# Charger.net
KiCad netlist of a schematic drawn in Altium Designer
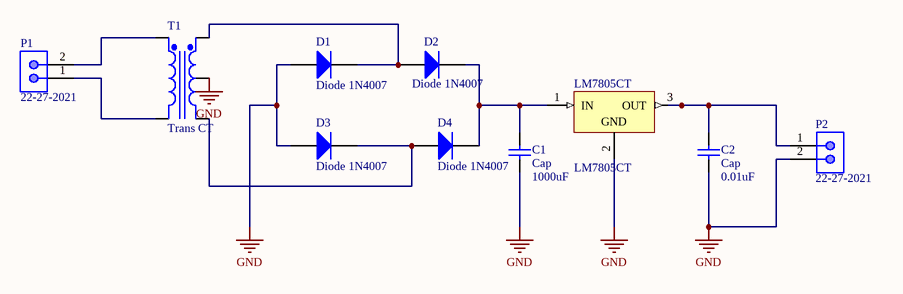
[diagram p0: Charger.SchDoc]

(export (version "E")
  (design (tool "Eeschema 10.0.6"))
  (components
    (comp (ref "C1")
      (value "Cap")
      (footprint "RAD-0.3")
      (description "Capacitor")
      (fields (field (name "ALTIUM_VALUE") "1000uF") (field (name "PUBLISHER") "Altium Limited"))
      (libsource (lib "Miscellaneous Devices") (part "Cap"))
    )
    (comp (ref "C2")
      (value "Cap")
      (footprint "RAD-0.3")
      (description "Capacitor")
      (fields (field (name "ALTIUM_VALUE") "0.01uF") (field (name "PUBLISHER") "Altium Limited"))
      (libsource (lib "Miscellaneous Devices") (part "Cap"))
    )
    (comp (ref "D1")
      (value "Diode 1N4007")
      (footprint "DO-41")
      (description "1 Amp General Purpose Rectifier")
      (fields (field (name "PUBLISHER") "Altium Limited"))
      (libsource (lib "Miscellaneous Devices") (part "Diode 1N4007"))
    )
    (comp (ref "D2")
      (value "Diode 1N4007")
      (footprint "DO-41")
      (description "1 Amp General Purpose Rectifier")
      (fields (field (name "PUBLISHER") "Altium Limited"))
      (libsource (lib "Miscellaneous Devices") (part "Diode 1N4007"))
    )
    (comp (ref "D3")
      (value "Diode 1N4007")
      (footprint "DO-41")
      (description "1 Amp General Purpose Rectifier")
      (fields (field (name "PUBLISHER") "Altium Limited"))
      (libsource (lib "Miscellaneous Devices") (part "Diode 1N4007"))
    )
    (comp (ref "D4")
      (value "Diode 1N4007")
      (footprint "DO-41")
      (description "1 Amp General Purpose Rectifier")
      (fields (field (name "PUBLISHER") "Altium Limited"))
      (libsource (lib "Miscellaneous Devices") (part "Diode 1N4007"))
    )
    (comp (ref "LM7805CT")
      (value "LM7805CT")
      (footprint "FAIR-TO-220-3")
      (description "Positive Voltage Regulator, 5 V, 1 A, -40 to 125 degC, 3-Pin TO-220, RoHS, Tube")
      (fields (field (name "MANUFACTURER") "FairchildSemiconductor"))
      (libsource (lib "Altium Content Vault") (part "FAIR-LM7805CT-TO220-3"))
    )
    (comp (ref "P1")
      (value "22-27-2021")
      (footprint "MOLX-22-27-2021_V")
      (fields (field (name "MANUFACTURER") "Molex") (field (name "PARTNUMBER") "0022272021"))
      (libsource (lib "Altium Content Vault") (part "CN-1P-M-R2"))
    )
    (comp (ref "P2")
      (value "22-27-2021")
      (footprint "MOLX-22-27-2021_V")
      (fields (field (name "MANUFACTURER") "Molex") (field (name "PARTNUMBER") "0022272021"))
      (libsource (lib "") (part "CN-1P-M-R2_1"))
    )
    (comp (ref "T1")
      (value "Trans CT")
      (footprint "TRF_5")
      (description "Center-Tapped Transformer (Coupled Inductor Model)")
      (fields (field (name "PUBLISHER") "Altium Limited"))
      (libsource (lib "Miscellaneous Devices") (part "Trans CT"))
    )
  )
  (nets
    (net (code "1") (name "GND") (class "Default")
      (node (ref "C1") (pin "1") (pinfunction "1_1") (pintype "passive"))
      (node (ref "C2") (pin "1") (pinfunction "1_1") (pintype "passive"))
      (node (ref "D1") (pin "1") (pinfunction "A_1") (pintype "passive"))
      (node (ref "D3") (pin "1") (pinfunction "A_1") (pintype "passive"))
      (node (ref "LM7805CT") (pin "2") (pinfunction "GND_2") (pintype "power_in"))
      (node (ref "P2") (pin "2") (pinfunction "2_2") (pintype "passive"))
      (node (ref "T1") (pin "4") (pinfunction "SecCT_4") (pintype "passive"))
    )
    (net (code "2") (name "Net-(D1-K)") (class "Default")
      (node (ref "D1") (pin "2") (pinfunction "K_2") (pintype "passive"))
      (node (ref "D2") (pin "1") (pinfunction "A_1") (pintype "passive"))
      (node (ref "T1") (pin "3") (pinfunction "Sec+_3") (pintype "passive"))
    )
    (net (code "3") (name "Net-(D2-K)") (class "Default")
      (node (ref "C1") (pin "2") (pinfunction "2_2") (pintype "passive"))
      (node (ref "D2") (pin "2") (pinfunction "K_2") (pintype "passive"))
      (node (ref "D4") (pin "2") (pinfunction "K_2") (pintype "passive"))
      (node (ref "LM7805CT") (pin "1") (pinfunction "IN_1") (pintype "input"))
    )
    (net (code "4") (name "Net-(D3-K)") (class "Default")
      (node (ref "D3") (pin "2") (pinfunction "K_2") (pintype "passive"))
      (node (ref "D4") (pin "1") (pinfunction "A_1") (pintype "passive"))
      (node (ref "T1") (pin "5") (pinfunction "Sec-_5") (pintype "passive"))
    )
    (net (code "5") (name "Net-(LM7805CT-OUT)") (class "Default")
      (node (ref "C2") (pin "2") (pinfunction "2_2") (pintype "passive"))
      (node (ref "LM7805CT") (pin "3") (pinfunction "OUT_3") (pintype "output"))
      (node (ref "P2") (pin "1") (pinfunction "1_1") (pintype "passive"))
    )
    (net (code "6") (name "Net-(T1-Pri+)") (class "Default")
      (node (ref "P1") (pin "2") (pinfunction "2_2") (pintype "passive"))
      (node (ref "T1") (pin "1") (pinfunction "Pri+_1") (pintype "passive"))
    )
    (net (code "7") (name "Net-(T1-Pri-)") (class "Default")
      (node (ref "P1") (pin "1") (pinfunction "1_1") (pintype "passive"))
      (node (ref "T1") (pin "2") (pinfunction "Pri-_2") (pintype "passive"))
    )
  )
)
